# HVAMP_8CH.net
KiCad netlist of a schematic drawn in Altium Designer
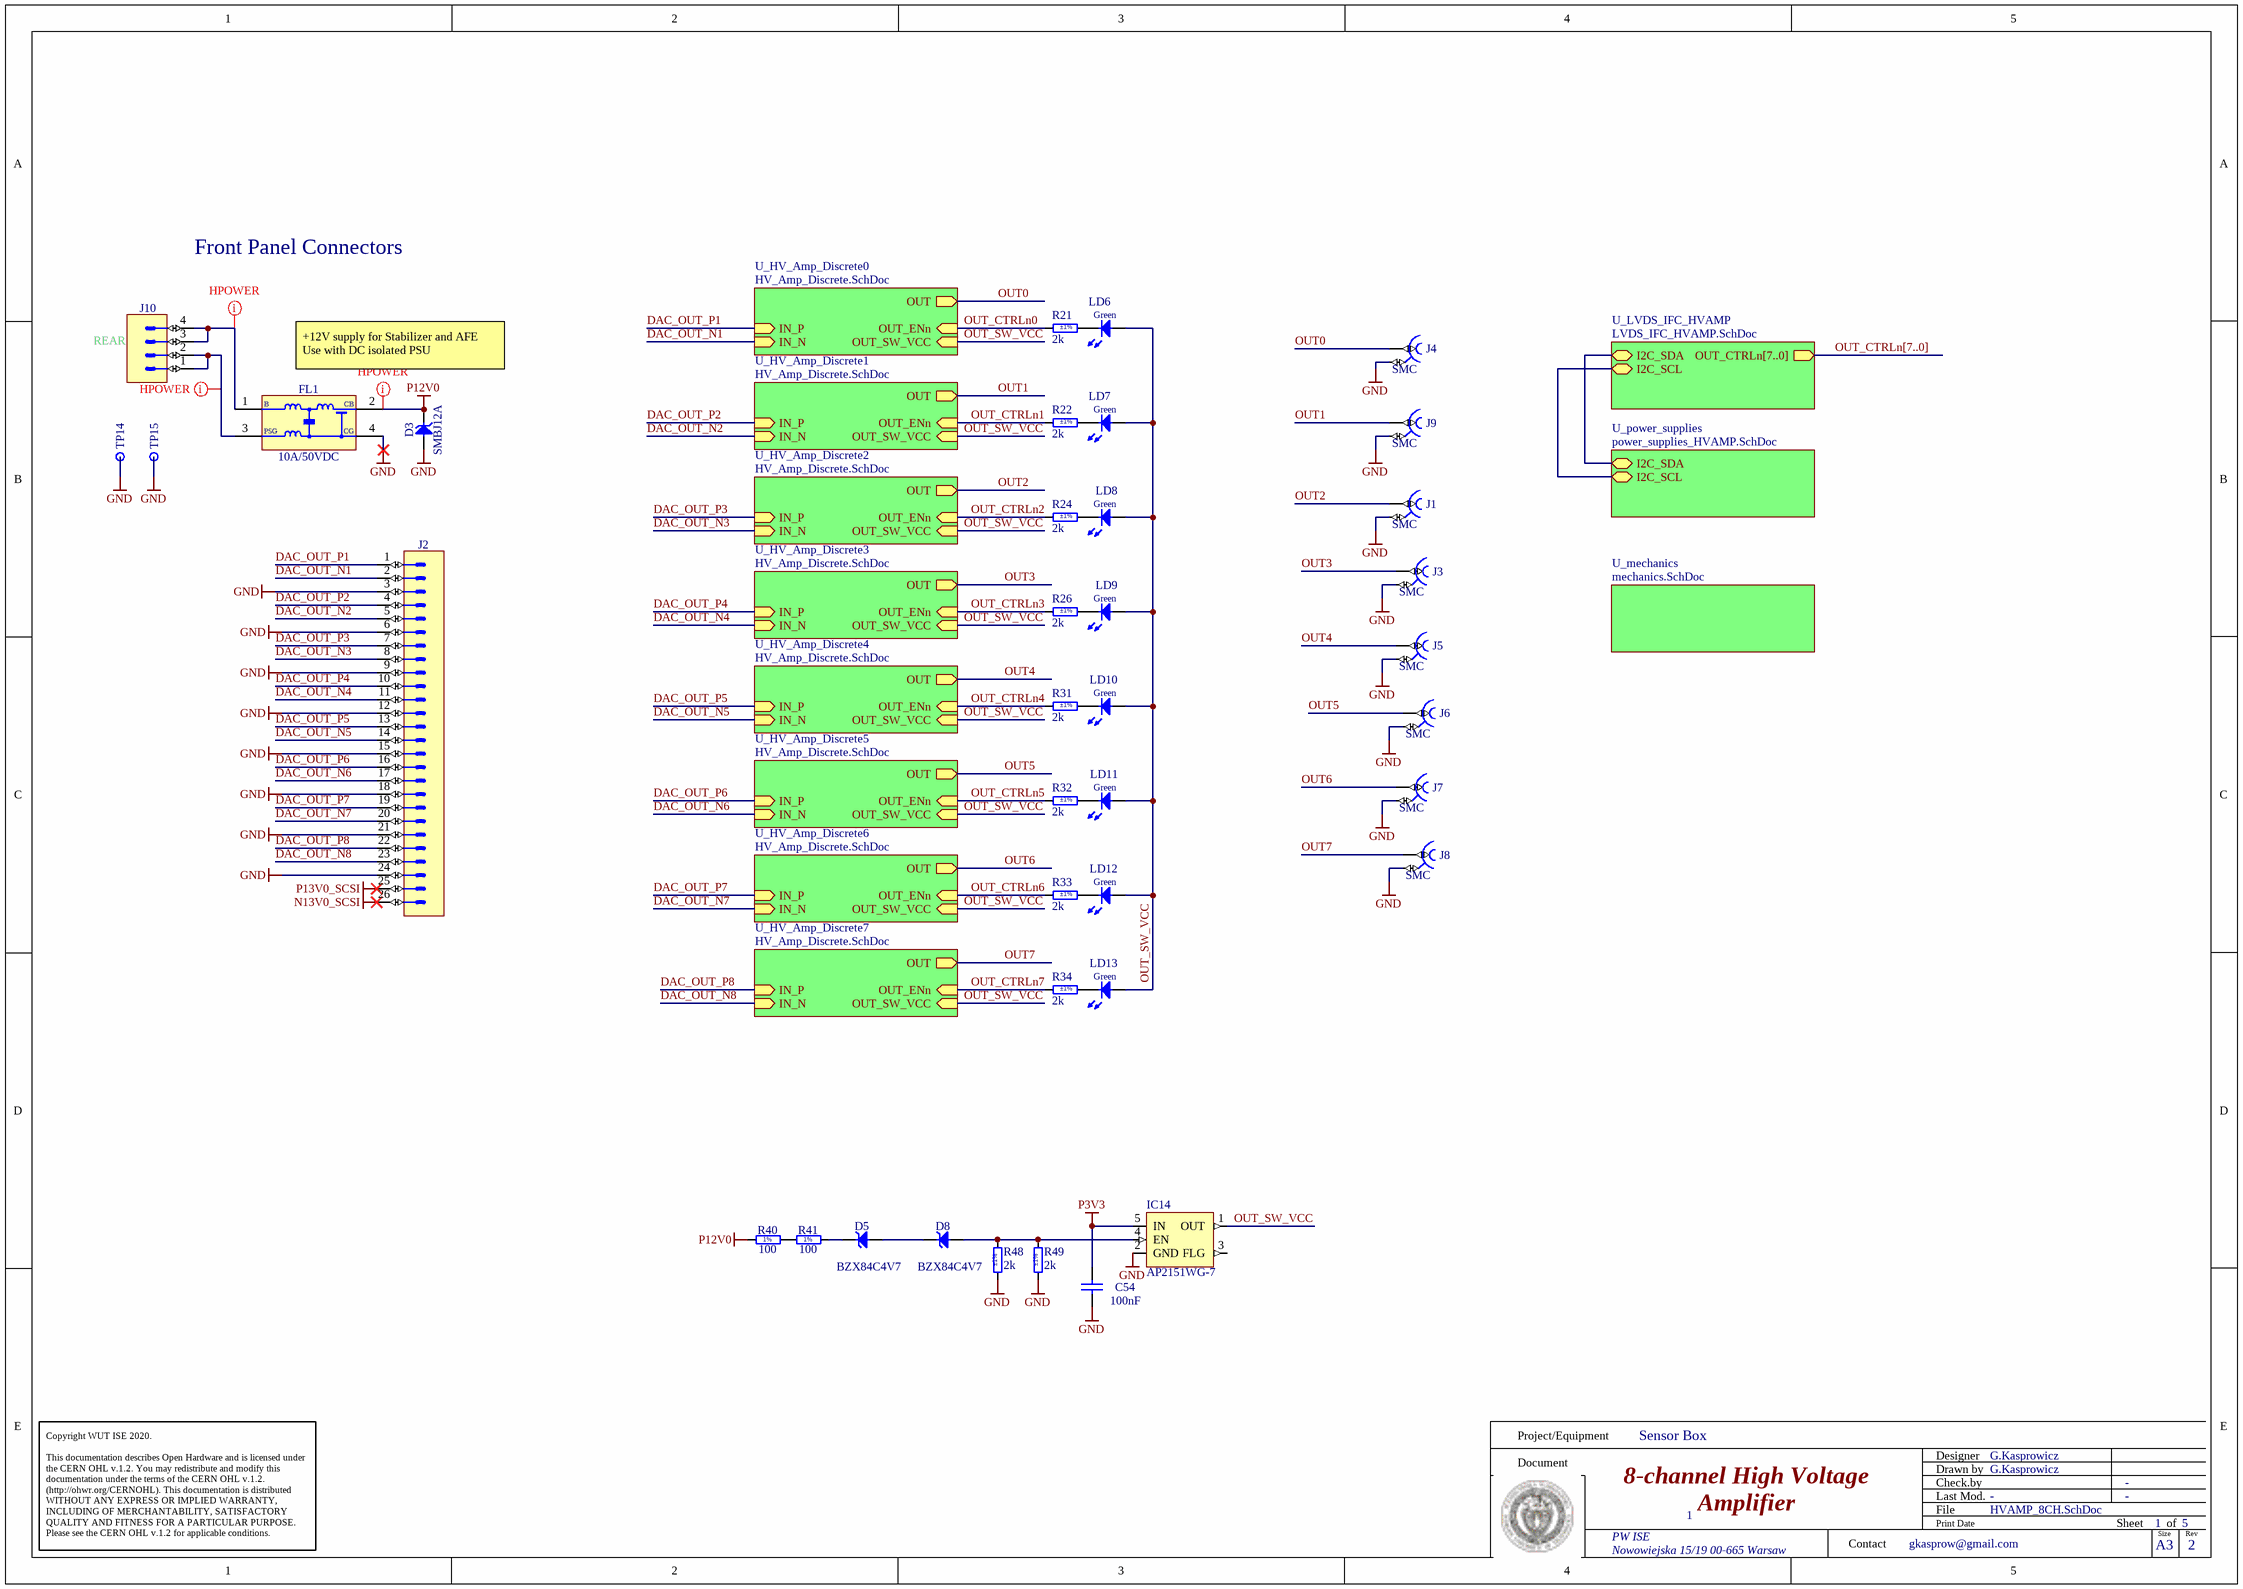
[diagram p0: HVAMP_8CH.SchDoc]

(export (version "E")
  (design (tool "Eeschema 10.0.6"))
  (components
    (comp (ref "C54")
      (value "100nF")
      (footprint "CAPC1005X55N")
      (description "Non-polarised capacitor")
      (fields
        (field (name "PART NUMBER") "CC0402_100NF_16V_10%_X5R")
        (field (name "VOLTAGE") "16V")
        (field (name "AUTHOR") "CERN DEM JLC")
      )
      (libsource (lib "Capacitors") (part "Capacitor - non polarized"))
    )
    (comp (ref "D3")
      (value "SMBJ12A")
      (footprint "DIOM5336X265N")
      (description "Zener Diode")
      (fields
        (field (name "VOLTAGE") "12V")
        (field (name "POWER") "600W")
        (field (name "AUTHOR") "CERN DEM JLC")
      )
      (libsource (lib "ICs And Semiconductors") (part "Diode Zener"))
    )
    (comp (ref "D5")
      (value "BZX84C4V7")
      (footprint "SOT95P240X130-3N")
      (description "Diode Zener Anode Pin 1 Cathode Pin 3 (Pas de pin 2)")
      (fields
        (field (name "VOLTAGE") "4V7")
        (field (name "POWER") "350mW")
        (field (name "AUTHOR") "CERN DEM JLC")
      )
      (libsource (lib "ICs And Semiconductors") (part "Diode Zener A1C3"))
    )
    (comp (ref "D8")
      (value "BZX84C4V7")
      (footprint "SOT95P240X130-3N")
      (description "Diode Zener Anode Pin 1 Cathode Pin 3 (Pas de pin 2)")
      (fields
        (field (name "VOLTAGE") "4V7")
        (field (name "POWER") "350mW")
        (field (name "AUTHOR") "CERN DEM JLC")
      )
      (libsource (lib "ICs And Semiconductors") (part "Diode Zener A1C3"))
    )
    (comp (ref "FL1")
      (value "10A/50VDC")
      (footprint "FIL_MURATA_BNX02")
      (description "Block Type EMIFIL (LC Combined)")
      (fields
        (field (name "PART NUMBER") "FIL_MURATA_BNX022-01L")
        (field (name "MANUFACTURER") "MURATA")
        (field (name "AUTHOR") "CERN DEM JLC")
      )
      (libsource (lib "Inductors & Transformers") (part "FIL_MURATA_BNX02"))
    )
    (comp (ref "IC14")
      (value "AP2151WG-7")
      (footprint "SOT23-5")
      (description "0.5A SINGLE CHANNEL CURRENT- LIMITED POWER Switch")
      (libsource (lib "ICs_Analog_Interfaces") (part "IFC_AP2151"))
    )
    (comp (ref "J1")
      (value "SMC")
      (footprint "JOHNSON_131-6701-341")
      (fields
        (field (name "PART NUMBER") "JOHNSON_131-6701-341")
        (field (name "MANUFACTURER") "JOHNSON")
        (field (name "MANUFACTURER PART NUMBER") "131-6701-341")
        (field (name "AUTHOR") "CERN DEM JLC")
      )
      (libsource (lib "Connectors") (part "Coax_1Female_1Shield"))
    )
    (comp (ref "J2")
      (value "Header 26")
      (footprint "3M_N2526-6002RB")
      (description "Connector 26 Male")
      (fields
        (field (name "PART NUMBER") "3M_N2526-6002RB")
        (field (name "MANUFACTURER") "3M")
        (field (name "AUTHOR") "CERN DEM JLC")
      )
      (libsource (lib "Connectors") (part "Connector 26 Male"))
    )
    (comp (ref "J3")
      (value "SMC")
      (footprint "JOHNSON_131-6701-341")
      (fields
        (field (name "PART NUMBER") "JOHNSON_131-6701-341")
        (field (name "MANUFACTURER") "JOHNSON")
        (field (name "MANUFACTURER PART NUMBER") "131-6701-341")
        (field (name "AUTHOR") "CERN DEM JLC")
      )
      (libsource (lib "Connectors") (part "Coax_1Female_1Shield"))
    )
    (comp (ref "J4")
      (value "SMC")
      (footprint "JOHNSON_131-6701-341")
      (fields
        (field (name "PART NUMBER") "JOHNSON_131-6701-341")
        (field (name "MANUFACTURER") "JOHNSON")
        (field (name "MANUFACTURER PART NUMBER") "131-6701-341")
        (field (name "AUTHOR") "CERN DEM JLC")
      )
      (libsource (lib "Connectors") (part "Coax_1Female_1Shield"))
    )
    (comp (ref "J5")
      (value "SMC")
      (footprint "JOHNSON_131-6701-341")
      (fields
        (field (name "PART NUMBER") "JOHNSON_131-6701-341")
        (field (name "MANUFACTURER") "JOHNSON")
        (field (name "MANUFACTURER PART NUMBER") "131-6701-341")
        (field (name "AUTHOR") "CERN DEM JLC")
      )
      (libsource (lib "Connectors") (part "Coax_1Female_1Shield"))
    )
    (comp (ref "J6")
      (value "SMC")
      (footprint "JOHNSON_131-6701-341")
      (fields
        (field (name "PART NUMBER") "JOHNSON_131-6701-341")
        (field (name "MANUFACTURER") "JOHNSON")
        (field (name "MANUFACTURER PART NUMBER") "131-6701-341")
        (field (name "AUTHOR") "CERN DEM JLC")
      )
      (libsource (lib "Connectors") (part "Coax_1Female_1Shield"))
    )
    (comp (ref "J7")
      (value "SMC")
      (footprint "JOHNSON_131-6701-341")
      (fields
        (field (name "PART NUMBER") "JOHNSON_131-6701-341")
        (field (name "MANUFACTURER") "JOHNSON")
        (field (name "MANUFACTURER PART NUMBER") "131-6701-341")
        (field (name "AUTHOR") "CERN DEM JLC")
      )
      (libsource (lib "Connectors") (part "Coax_1Female_1Shield"))
    )
    (comp (ref "J8")
      (value "SMC")
      (footprint "JOHNSON_131-6701-341")
      (fields
        (field (name "PART NUMBER") "JOHNSON_131-6701-341")
        (field (name "MANUFACTURER") "JOHNSON")
        (field (name "MANUFACTURER PART NUMBER") "131-6701-341")
        (field (name "AUTHOR") "CERN DEM JLC")
      )
      (libsource (lib "Connectors") (part "Coax_1Female_1Shield"))
    )
    (comp (ref "J9")
      (value "SMC")
      (footprint "JOHNSON_131-6701-341")
      (fields
        (field (name "PART NUMBER") "JOHNSON_131-6701-341")
        (field (name "MANUFACTURER") "JOHNSON")
        (field (name "MANUFACTURER PART NUMBER") "131-6701-341")
        (field (name "AUTHOR") "CERN DEM JLC")
      )
      (libsource (lib "Connectors") (part "Coax_1Female_1Shield"))
    )
    (comp (ref "J10")
      (value "Mini-Fit Jr.™")
      (footprint "MOLEX_39-30-0040")
      (description "Connector 4 Male")
      (fields
        (field (name "PART NUMBER") "MOLEX_39-30-0040")
        (field (name "MANUFACTURER") "MOLEX")
        (field (name "AUTHOR") "CERN DEM JLC")
      )
      (libsource (lib "Connectors") (part "Connector 4 Male"))
    )
    (comp (ref "LD6")
      (value "Green")
      (footprint "LED_AVAGO_HSME-C120")
      (description "LED Green 1C 2A")
      (fields
        (field (name "PART NUMBER") "LED_AVAGO_HSME-C120")
        (field (name "MANUFACTURER") "AVAGO TECHNOLOGIES")
        (field (name "AUTHOR") "CERN DEM JMW")
      )
      (libsource (lib "ICs And Semiconductors") (part "LED Green 1C 2A"))
    )
    (comp (ref "LD7")
      (value "Green")
      (footprint "LED_AVAGO_HSME-C120")
      (description "LED Green 1C 2A")
      (fields
        (field (name "PART NUMBER") "LED_AVAGO_HSME-C120")
        (field (name "MANUFACTURER") "AVAGO TECHNOLOGIES")
        (field (name "AUTHOR") "CERN DEM JMW")
      )
      (libsource (lib "ICs And Semiconductors") (part "LED Green 1C 2A"))
    )
    (comp (ref "LD8")
      (value "Green")
      (footprint "LED_AVAGO_HSME-C120")
      (description "LED Green 1C 2A")
      (fields
        (field (name "PART NUMBER") "LED_AVAGO_HSME-C120")
        (field (name "MANUFACTURER") "AVAGO TECHNOLOGIES")
        (field (name "AUTHOR") "CERN DEM JMW")
      )
      (libsource (lib "ICs And Semiconductors") (part "LED Green 1C 2A"))
    )
    (comp (ref "LD9")
      (value "Green")
      (footprint "LED_AVAGO_HSME-C120")
      (description "LED Green 1C 2A")
      (fields
        (field (name "PART NUMBER") "LED_AVAGO_HSME-C120")
        (field (name "MANUFACTURER") "AVAGO TECHNOLOGIES")
        (field (name "AUTHOR") "CERN DEM JMW")
      )
      (libsource (lib "ICs And Semiconductors") (part "LED Green 1C 2A"))
    )
    (comp (ref "LD10")
      (value "Green")
      (footprint "LED_AVAGO_HSME-C120")
      (description "LED Green 1C 2A")
      (fields
        (field (name "PART NUMBER") "LED_AVAGO_HSME-C120")
        (field (name "MANUFACTURER") "AVAGO TECHNOLOGIES")
        (field (name "AUTHOR") "CERN DEM JMW")
      )
      (libsource (lib "ICs And Semiconductors") (part "LED Green 1C 2A"))
    )
    (comp (ref "LD11")
      (value "Green")
      (footprint "LED_AVAGO_HSME-C120")
      (description "LED Green 1C 2A")
      (fields
        (field (name "PART NUMBER") "LED_AVAGO_HSME-C120")
        (field (name "MANUFACTURER") "AVAGO TECHNOLOGIES")
        (field (name "AUTHOR") "CERN DEM JMW")
      )
      (libsource (lib "ICs And Semiconductors") (part "LED Green 1C 2A"))
    )
    (comp (ref "LD12")
      (value "Green")
      (footprint "LED_AVAGO_HSME-C120")
      (description "LED Green 1C 2A")
      (fields
        (field (name "PART NUMBER") "LED_AVAGO_HSME-C120")
        (field (name "MANUFACTURER") "AVAGO TECHNOLOGIES")
        (field (name "AUTHOR") "CERN DEM JMW")
      )
      (libsource (lib "ICs And Semiconductors") (part "LED Green 1C 2A"))
    )
    (comp (ref "LD13")
      (value "Green")
      (footprint "LED_AVAGO_HSME-C120")
      (description "LED Green 1C 2A")
      (fields
        (field (name "PART NUMBER") "LED_AVAGO_HSME-C120")
        (field (name "MANUFACTURER") "AVAGO TECHNOLOGIES")
        (field (name "AUTHOR") "CERN DEM JMW")
      )
      (libsource (lib "ICs And Semiconductors") (part "LED Green 1C 2A"))
    )
    (comp (ref "R21")
      (value "2k")
      (footprint "RESC1005X40N")
      (description "Resistor - 1%")
      (fields
        (field (name "PART NUMBER") "R0402_2K_1%_0.0625W_100PPM")
        (field (name "POWER") "0.0625W")
        (field (name "TOLERANCE") "±1%")
        (field (name "AUTHOR") "CERN DEM JLC")
      )
      (libsource (lib "Resistors") (part "Resistor - 1%"))
    )
    (comp (ref "R22")
      (value "2k")
      (footprint "RESC1005X40N")
      (description "Resistor - 1%")
      (fields
        (field (name "PART NUMBER") "R0402_2K_1%_0.0625W_100PPM")
        (field (name "POWER") "0.0625W")
        (field (name "TOLERANCE") "±1%")
        (field (name "AUTHOR") "CERN DEM JLC")
      )
      (libsource (lib "Resistors") (part "Resistor - 1%"))
    )
    (comp (ref "R24")
      (value "2k")
      (footprint "RESC1005X40N")
      (description "Resistor - 1%")
      (fields
        (field (name "PART NUMBER") "R0402_2K_1%_0.0625W_100PPM")
        (field (name "POWER") "0.0625W")
        (field (name "TOLERANCE") "±1%")
        (field (name "AUTHOR") "CERN DEM JLC")
      )
      (libsource (lib "Resistors") (part "Resistor - 1%"))
    )
    (comp (ref "R26")
      (value "2k")
      (footprint "RESC1005X40N")
      (description "Resistor - 1%")
      (fields
        (field (name "PART NUMBER") "R0402_2K_1%_0.0625W_100PPM")
        (field (name "POWER") "0.0625W")
        (field (name "TOLERANCE") "±1%")
        (field (name "AUTHOR") "CERN DEM JLC")
      )
      (libsource (lib "Resistors") (part "Resistor - 1%"))
    )
    (comp (ref "R31")
      (value "2k")
      (footprint "RESC1005X40N")
      (description "Resistor - 1%")
      (fields
        (field (name "PART NUMBER") "R0402_2K_1%_0.0625W_100PPM")
        (field (name "POWER") "0.0625W")
        (field (name "TOLERANCE") "±1%")
        (field (name "AUTHOR") "CERN DEM JLC")
      )
      (libsource (lib "Resistors") (part "Resistor - 1%"))
    )
    (comp (ref "R32")
      (value "2k")
      (footprint "RESC1005X40N")
      (description "Resistor - 1%")
      (fields
        (field (name "PART NUMBER") "R0402_2K_1%_0.0625W_100PPM")
        (field (name "POWER") "0.0625W")
        (field (name "TOLERANCE") "±1%")
        (field (name "AUTHOR") "CERN DEM JLC")
      )
      (libsource (lib "Resistors") (part "Resistor - 1%"))
    )
    (comp (ref "R33")
      (value "2k")
      (footprint "RESC1005X40N")
      (description "Resistor - 1%")
      (fields
        (field (name "PART NUMBER") "R0402_2K_1%_0.0625W_100PPM")
        (field (name "POWER") "0.0625W")
        (field (name "TOLERANCE") "±1%")
        (field (name "AUTHOR") "CERN DEM JLC")
      )
      (libsource (lib "Resistors") (part "Resistor - 1%"))
    )
    (comp (ref "R34")
      (value "2k")
      (footprint "RESC1005X40N")
      (description "Resistor - 1%")
      (fields
        (field (name "PART NUMBER") "R0402_2K_1%_0.0625W_100PPM")
        (field (name "POWER") "0.0625W")
        (field (name "TOLERANCE") "±1%")
        (field (name "AUTHOR") "CERN DEM JLC")
      )
      (libsource (lib "Resistors") (part "Resistor - 1%"))
    )
    (comp (ref "R40")
      (value "100")
      (footprint "RESC1005X40N")
      (description "Resistor - 1%")
      (fields
        (field (name "PART NUMBER") "R0402_100R_1%_0.0625W_100PPM")
        (field (name "POWER") "0.0625W")
        (field (name "AUTHOR") "CERN DEM JLC")
      )
      (libsource (lib "Resistors") (part "Resistor - 1%"))
    )
    (comp (ref "R41")
      (value "100")
      (footprint "RESC1005X40N")
      (description "Resistor - 1%")
      (fields
        (field (name "PART NUMBER") "R0402_100R_1%_0.0625W_100PPM")
        (field (name "POWER") "0.0625W")
        (field (name "AUTHOR") "CERN DEM JLC")
      )
      (libsource (lib "Resistors") (part "Resistor - 1%"))
    )
    (comp (ref "R48")
      (value "2k")
      (footprint "RESC1005X40N")
      (description "Resistor - 1%")
      (fields
        (field (name "PART NUMBER") "R0402_2K_1%_0.0625W_100PPM")
        (field (name "POWER") "0.0625W")
        (field (name "TOLERANCE") "±1%")
        (field (name "AUTHOR") "CERN DEM JLC")
      )
      (libsource (lib "Resistors") (part "Resistor - 1%"))
    )
    (comp (ref "R49")
      (value "2k")
      (footprint "RESC1005X40N")
      (description "Resistor - 1%")
      (fields
        (field (name "PART NUMBER") "R0402_2K_1%_0.0625W_100PPM")
        (field (name "POWER") "0.0625W")
        (field (name "TOLERANCE") "±1%")
        (field (name "AUTHOR") "CERN DEM JLC")
      )
      (libsource (lib "Resistors") (part "Resistor - 1%"))
    )
    (comp (ref "TP14")
      (value "Test Point")
      (footprint "TPS127")
      (fields (field (name "PART NUMBER") "SMD_PAD_1.27X1.27MM") (field (name "AUTHOR") "CERN DEM JLC"))
      (libsource (lib "Eletro-mechanical") (part "Test Point"))
    )
    (comp (ref "TP15")
      (value "Test Point")
      (footprint "TPS127")
      (fields (field (name "PART NUMBER") "SMD_PAD_1.27X1.27MM") (field (name "AUTHOR") "CERN DEM JLC"))
      (libsource (lib "Eletro-mechanical") (part "Test Point"))
    )
  )
  (nets
    (net (code "1") (name "/DAC_OUT_N1") (class "Default")
      (node (ref "J2") (pin "2") (pinfunction "2_2") (pintype "bidirectional"))
    )
    (net (code "2") (name "/DAC_OUT_N2") (class "Default")
      (node (ref "J2") (pin "5") (pinfunction "5_5") (pintype "bidirectional"))
    )
    (net (code "3") (name "/DAC_OUT_N3") (class "Default")
      (node (ref "J2") (pin "8") (pinfunction "8_8") (pintype "bidirectional"))
    )
    (net (code "4") (name "/DAC_OUT_N4") (class "Default")
      (node (ref "J2") (pin "11") (pinfunction "11_11") (pintype "bidirectional"))
    )
    (net (code "5") (name "/DAC_OUT_N5") (class "Default")
      (node (ref "J2") (pin "14") (pinfunction "14_14") (pintype "bidirectional"))
    )
    (net (code "6") (name "/DAC_OUT_N6") (class "Default")
      (node (ref "J2") (pin "17") (pinfunction "17_17") (pintype "bidirectional"))
    )
    (net (code "7") (name "/DAC_OUT_N7") (class "Default")
      (node (ref "J2") (pin "20") (pinfunction "20_20") (pintype "bidirectional"))
    )
    (net (code "8") (name "/DAC_OUT_N8") (class "Default")
      (node (ref "J2") (pin "23") (pinfunction "23_23") (pintype "bidirectional"))
    )
    (net (code "9") (name "/DAC_OUT_P1") (class "Default")
      (node (ref "J2") (pin "1") (pinfunction "1_1") (pintype "bidirectional"))
    )
    (net (code "10") (name "/DAC_OUT_P2") (class "Default")
      (node (ref "J2") (pin "4") (pinfunction "4_4") (pintype "bidirectional"))
    )
    (net (code "11") (name "/DAC_OUT_P3") (class "Default")
      (node (ref "J2") (pin "7") (pinfunction "7_7") (pintype "bidirectional"))
    )
    (net (code "12") (name "/DAC_OUT_P4") (class "Default")
      (node (ref "J2") (pin "10") (pinfunction "10_10") (pintype "bidirectional"))
    )
    (net (code "13") (name "/DAC_OUT_P5") (class "Default")
      (node (ref "J2") (pin "13") (pinfunction "13_13") (pintype "bidirectional"))
    )
    (net (code "14") (name "/DAC_OUT_P6") (class "Default")
      (node (ref "J2") (pin "16") (pinfunction "16_16") (pintype "bidirectional"))
    )
    (net (code "15") (name "/DAC_OUT_P7") (class "Default")
      (node (ref "J2") (pin "19") (pinfunction "19_19") (pintype "bidirectional"))
    )
    (net (code "16") (name "/DAC_OUT_P8") (class "Default")
      (node (ref "J2") (pin "22") (pinfunction "22_22") (pintype "bidirectional"))
    )
    (net (code "19") (name "/OUT0") (class "Default")
      (node (ref "J4") (pin "1") (pinfunction "1_1") (pintype "bidirectional"))
    )
    (net (code "20") (name "/OUT1") (class "Default")
      (node (ref "J9") (pin "1") (pinfunction "1_1") (pintype "bidirectional"))
    )
    (net (code "21") (name "/OUT2") (class "Default")
      (node (ref "J1") (pin "1") (pinfunction "1_1") (pintype "bidirectional"))
    )
    (net (code "22") (name "/OUT3") (class "Default")
      (node (ref "J3") (pin "1") (pinfunction "1_1") (pintype "bidirectional"))
    )
    (net (code "23") (name "/OUT4") (class "Default")
      (node (ref "J5") (pin "1") (pinfunction "1_1") (pintype "bidirectional"))
    )
    (net (code "24") (name "/OUT5") (class "Default")
      (node (ref "J6") (pin "1") (pinfunction "1_1") (pintype "bidirectional"))
    )
    (net (code "25") (name "/OUT6") (class "Default")
      (node (ref "J7") (pin "1") (pinfunction "1_1") (pintype "bidirectional"))
    )
    (net (code "26") (name "/OUT7") (class "Default")
      (node (ref "J8") (pin "1") (pinfunction "1_1") (pintype "bidirectional"))
    )
    (net (code "27") (name "/OUT_CTRLn0") (class "Default")
      (node (ref "R21") (pin "2") (pinfunction "2_2") (pintype "passive"))
    )
    (net (code "28") (name "/OUT_CTRLn1") (class "Default")
      (node (ref "R22") (pin "2") (pinfunction "2_2") (pintype "passive"))
    )
    (net (code "29") (name "/OUT_CTRLn2") (class "Default")
      (node (ref "R24") (pin "2") (pinfunction "2_2") (pintype "passive"))
    )
    (net (code "30") (name "/OUT_CTRLn3") (class "Default")
      (node (ref "R26") (pin "2") (pinfunction "2_2") (pintype "passive"))
    )
    (net (code "31") (name "/OUT_CTRLn4") (class "Default")
      (node (ref "R31") (pin "2") (pinfunction "2_2") (pintype "passive"))
    )
    (net (code "32") (name "/OUT_CTRLn5") (class "Default")
      (node (ref "R32") (pin "2") (pinfunction "2_2") (pintype "passive"))
    )
    (net (code "33") (name "/OUT_CTRLn6") (class "Default")
      (node (ref "R33") (pin "2") (pinfunction "2_2") (pintype "passive"))
    )
    (net (code "34") (name "/OUT_CTRLn7") (class "Default")
      (node (ref "R34") (pin "2") (pinfunction "2_2") (pintype "passive"))
    )
    (net (code "36") (name "/OUT_SW_VCC") (class "Default")
      (node (ref "IC14") (pin "1") (pinfunction "OUT_1") (pintype "output"))
      (node (ref "LD10") (pin "2") (pinfunction "A_2") (pintype "passive"))
      (node (ref "LD11") (pin "2") (pinfunction "A_2") (pintype "passive"))
      (node (ref "LD12") (pin "2") (pinfunction "A_2") (pintype "passive"))
      (node (ref "LD13") (pin "2") (pinfunction "A_2") (pintype "passive"))
      (node (ref "LD6") (pin "2") (pinfunction "A_2") (pintype "passive"))
      (node (ref "LD7") (pin "2") (pinfunction "A_2") (pintype "passive"))
      (node (ref "LD8") (pin "2") (pinfunction "A_2") (pintype "passive"))
      (node (ref "LD9") (pin "2") (pinfunction "A_2") (pintype "passive"))
    )
    (net (code "37") (name "GND") (class "Default")
      (node (ref "C54") (pin "1") (pinfunction "1_1") (pintype "passive"))
      (node (ref "D3") (pin "2") (pinfunction "A_2") (pintype "passive"))
      (node (ref "FL1") (pin "4") (pinfunction "CG_4") (pintype "passive"))
      (node (ref "IC14") (pin "2") (pinfunction "GND_2") (pintype "power_in"))
      (node (ref "J1") (pin "2") (pinfunction "2_2") (pintype "bidirectional"))
      (node (ref "J2") (pin "12") (pinfunction "12_12") (pintype "bidirectional"))
      (node (ref "J2") (pin "15") (pinfunction "15_15") (pintype "bidirectional"))
      (node (ref "J2") (pin "18") (pinfunction "18_18") (pintype "bidirectional"))
      (node (ref "J2") (pin "21") (pinfunction "21_21") (pintype "bidirectional"))
      (node (ref "J2") (pin "24") (pinfunction "24_24") (pintype "bidirectional"))
      (node (ref "J2") (pin "3") (pinfunction "3_3") (pintype "bidirectional"))
      (node (ref "J2") (pin "6") (pinfunction "6_6") (pintype "bidirectional"))
      (node (ref "J2") (pin "9") (pinfunction "9_9") (pintype "bidirectional"))
      (node (ref "J3") (pin "2") (pinfunction "2_2") (pintype "bidirectional"))
      (node (ref "J4") (pin "2") (pinfunction "2_2") (pintype "bidirectional"))
      (node (ref "J5") (pin "2") (pinfunction "2_2") (pintype "bidirectional"))
      (node (ref "J6") (pin "2") (pinfunction "2_2") (pintype "bidirectional"))
      (node (ref "J7") (pin "2") (pinfunction "2_2") (pintype "bidirectional"))
      (node (ref "J8") (pin "2") (pinfunction "2_2") (pintype "bidirectional"))
      (node (ref "J9") (pin "2") (pinfunction "2_2") (pintype "bidirectional"))
      (node (ref "R48") (pin "2") (pinfunction "2_2") (pintype "passive"))
      (node (ref "R49") (pin "2") (pinfunction "2_2") (pintype "passive"))
      (node (ref "TP14") (pin "1") (pinfunction "1_1") (pintype "bidirectional"))
      (node (ref "TP15") (pin "1") (pinfunction "1_1") (pintype "bidirectional"))
    )
    (net (code "38") (name "N13V0_SCSI") (class "Default")
      (node (ref "J2") (pin "26") (pinfunction "26_26") (pintype "bidirectional"))
    )
    (net (code "39") (name "Net-(D5-A)") (class "Default")
      (node (ref "D5") (pin "1") (pinfunction "A_1") (pintype "passive"))
      (node (ref "D8") (pin "3") (pinfunction "C_3") (pintype "passive"))
    )
    (net (code "40") (name "Net-(D5-C)") (class "Default")
      (node (ref "D5") (pin "3") (pinfunction "C_3") (pintype "passive"))
      (node (ref "R41") (pin "2") (pinfunction "2_2") (pintype "passive"))
    )
    (net (code "41") (name "Net-(D8-A)") (class "Default")
      (node (ref "D8") (pin "1") (pinfunction "A_1") (pintype "passive"))
      (node (ref "IC14") (pin "4") (pinfunction "EN_4") (pintype "input"))
      (node (ref "R48") (pin "1") (pinfunction "1_1") (pintype "passive"))
      (node (ref "R49") (pin "1") (pinfunction "1_1") (pintype "passive"))
    )
    (net (code "42") (name "Net-(FL1-B)") (class "Default")
      (node (ref "FL1") (pin "1") (pinfunction "B_1") (pintype "passive"))
      (node (ref "J10") (pin "3") (pinfunction "3_3") (pintype "bidirectional"))
      (node (ref "J10") (pin "4") (pinfunction "4_4") (pintype "bidirectional"))
    )
    (net (code "43") (name "Net-(FL1-PSG)") (class "Default")
      (node (ref "FL1") (pin "3") (pinfunction "PSG_3") (pintype "passive"))
      (node (ref "J10") (pin "1") (pinfunction "1_1") (pintype "bidirectional"))
      (node (ref "J10") (pin "2") (pinfunction "2_2") (pintype "bidirectional"))
    )
    (net (code "44") (name "Net-(LD6-C)") (class "Default")
      (node (ref "LD6") (pin "1") (pinfunction "C_1") (pintype "passive"))
      (node (ref "R21") (pin "1") (pinfunction "1_1") (pintype "passive"))
    )
    (net (code "45") (name "Net-(LD7-C)") (class "Default")
      (node (ref "LD7") (pin "1") (pinfunction "C_1") (pintype "passive"))
      (node (ref "R22") (pin "1") (pinfunction "1_1") (pintype "passive"))
    )
    (net (code "46") (name "Net-(LD8-C)") (class "Default")
      (node (ref "LD8") (pin "1") (pinfunction "C_1") (pintype "passive"))
      (node (ref "R24") (pin "1") (pinfunction "1_1") (pintype "passive"))
    )
    (net (code "47") (name "Net-(LD9-C)") (class "Default")
      (node (ref "LD9") (pin "1") (pinfunction "C_1") (pintype "passive"))
      (node (ref "R26") (pin "1") (pinfunction "1_1") (pintype "passive"))
    )
    (net (code "48") (name "Net-(LD10-C)") (class "Default")
      (node (ref "LD10") (pin "1") (pinfunction "C_1") (pintype "passive"))
      (node (ref "R31") (pin "1") (pinfunction "1_1") (pintype "passive"))
    )
    (net (code "49") (name "Net-(LD11-C)") (class "Default")
      (node (ref "LD11") (pin "1") (pinfunction "C_1") (pintype "passive"))
      (node (ref "R32") (pin "1") (pinfunction "1_1") (pintype "passive"))
    )
    (net (code "50") (name "Net-(LD12-C)") (class "Default")
      (node (ref "LD12") (pin "1") (pinfunction "C_1") (pintype "passive"))
      (node (ref "R33") (pin "1") (pinfunction "1_1") (pintype "passive"))
    )
    (net (code "51") (name "Net-(LD13-C)") (class "Default")
      (node (ref "LD13") (pin "1") (pinfunction "C_1") (pintype "passive"))
      (node (ref "R34") (pin "1") (pinfunction "1_1") (pintype "passive"))
    )
    (net (code "52") (name "Net-(R40-Pad2)") (class "Default")
      (node (ref "R40") (pin "2") (pinfunction "2_2") (pintype "passive"))
      (node (ref "R41") (pin "1") (pinfunction "1_1") (pintype "passive"))
    )
    (net (code "53") (name "P3V3") (class "Default")
      (node (ref "C54") (pin "2") (pinfunction "2_2") (pintype "passive"))
      (node (ref "IC14") (pin "5") (pinfunction "IN_5") (pintype "power_in"))
    )
    (net (code "54") (name "P12V0") (class "Default")
      (node (ref "D3") (pin "1") (pinfunction "C_1") (pintype "passive"))
      (node (ref "FL1") (pin "2") (pinfunction "CB_2") (pintype "passive"))
      (node (ref "R40") (pin "1") (pinfunction "1_1") (pintype "passive"))
    )
    (net (code "55") (name "P13V0_SCSI") (class "Default")
      (node (ref "J2") (pin "25") (pinfunction "25_25") (pintype "bidirectional"))
    )
    (net (code "56") (name "unconnected-(IC14-FLG-Pad3)") (class "Default")
      (node (ref "IC14") (pin "3") (pinfunction "FLG_3") (pintype "output"))
    )
  )
)
